# working.net
KiCad netlist of a schematic drawn in EAGLE
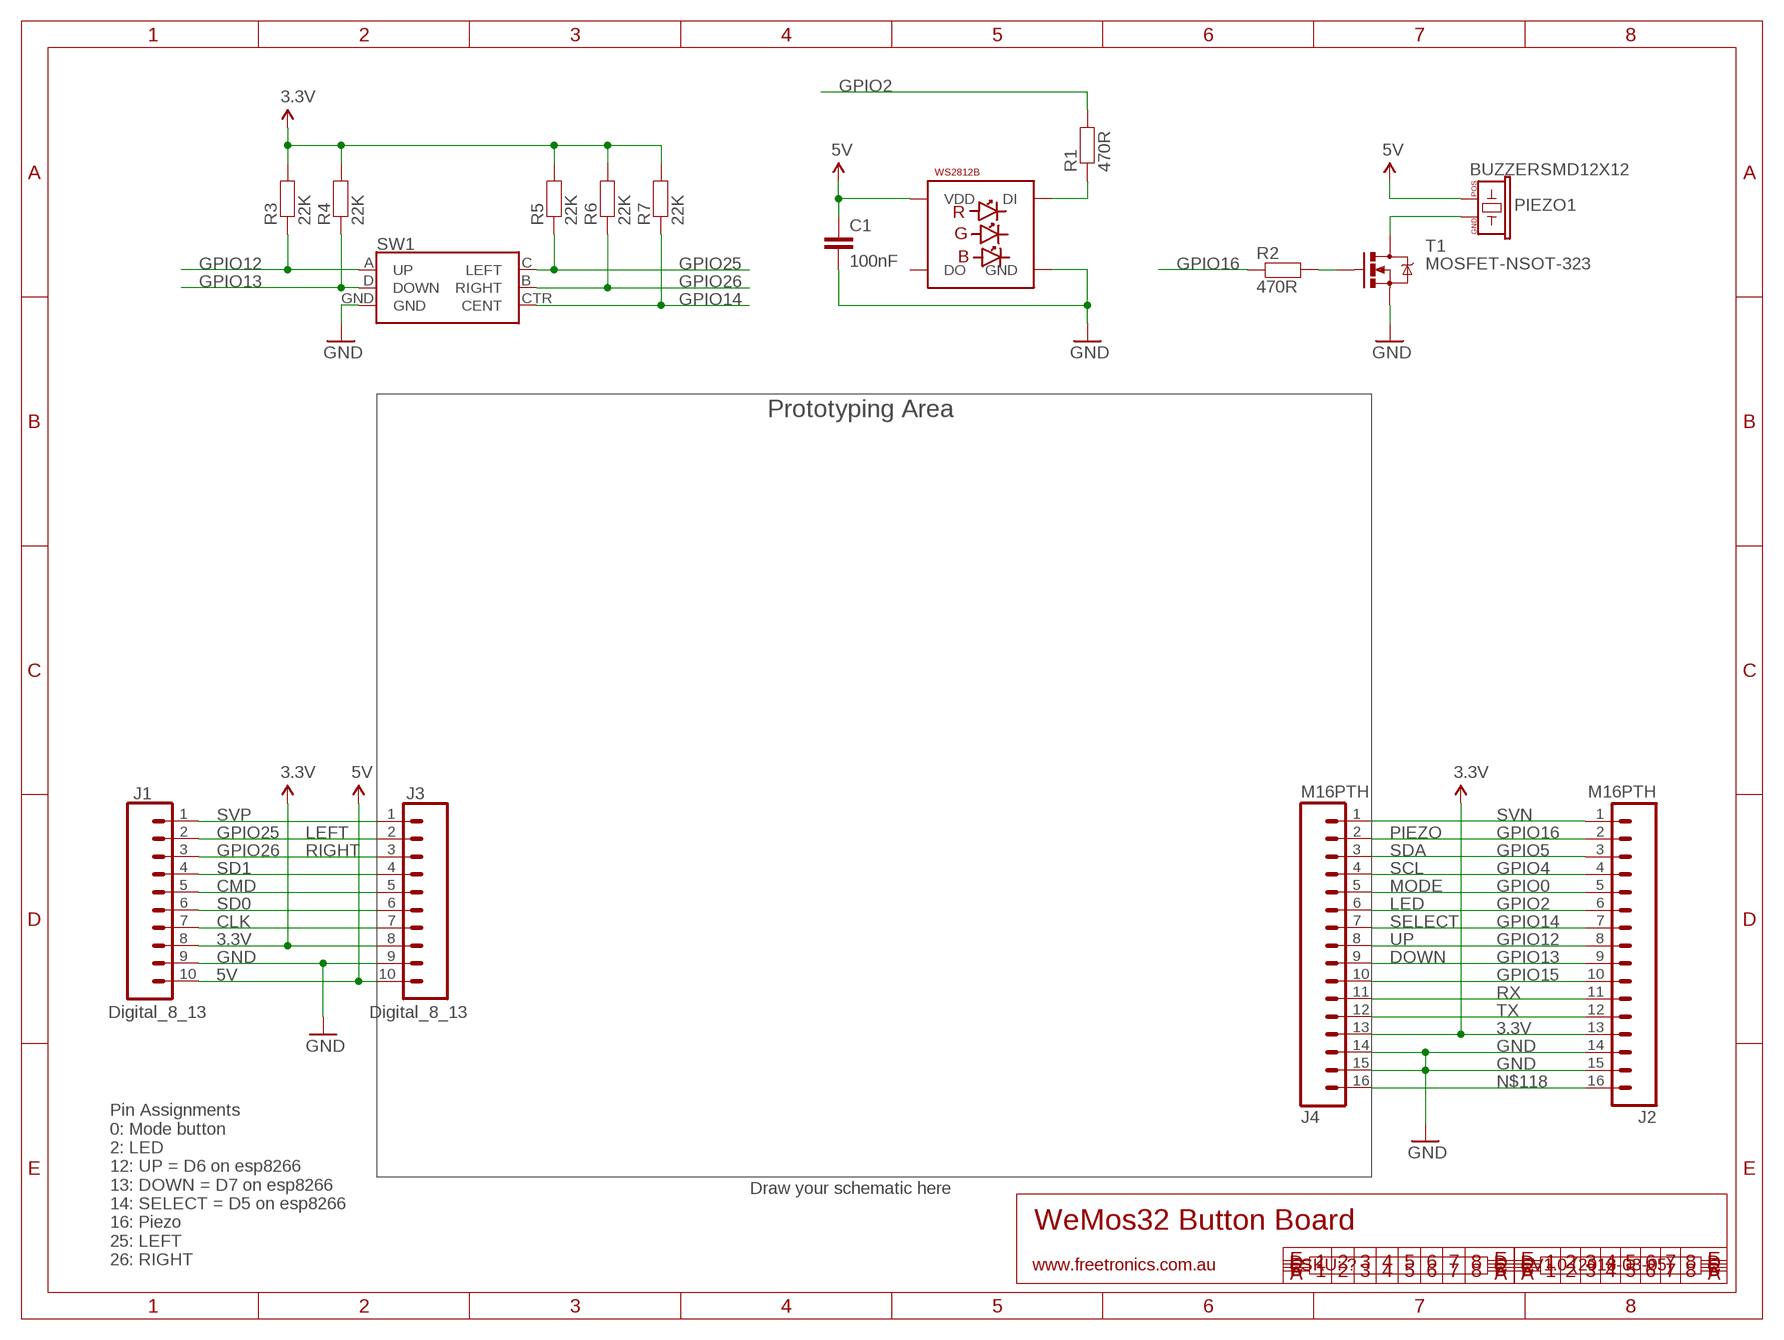
[diagram p0: schematic, sheet 1]

(export (version "E")
  (design (tool "Eeschema 10.0.6"))
  (components
    (comp (ref "C1")
      (value "100nF")
      (footprint "eagle-import:0603")
      (libsource (lib "eagle-import") (part "CAP0603"))
    )
    (comp (ref "J1")
      (value "Digital_8_13")
      (footprint "eagle-import:1X10")
      (libsource (lib "eagle-import") (part "M100.1"))
    )
    (comp (ref "J2")
      (value "M16PTH")
      (footprint "eagle-import:1X16")
      (libsource (lib "eagle-import") (part "M16PTH"))
    )
    (comp (ref "J3")
      (value "Digital_8_13")
      (footprint "eagle-import:1X10")
      (libsource (lib "eagle-import") (part "M100.1"))
    )
    (comp (ref "J4")
      (value "M16PTH")
      (footprint "eagle-import:1X16")
      (libsource (lib "eagle-import") (part "M16PTH"))
    )
    (comp (ref "LED2")
      (value "WS2812B5050")
      (footprint "eagle-import:WS2812B")
      (libsource (lib "eagle-import") (part "WS2812B5050"))
    )
    (comp (ref "PIEZO1")
      (value "BUZZERSMD12X12")
      (footprint "eagle-import:BUZZER-12X12-SMT")
      (libsource (lib "eagle-import") (part "BUZZERSMD12X12"))
    )
    (comp (ref "R1")
      (value "470R")
      (footprint "eagle-import:0603")
      (libsource (lib "eagle-import") (part "RESISTOR0603"))
    )
    (comp (ref "R2")
      (value "470R")
      (footprint "eagle-import:0603")
      (libsource (lib "eagle-import") (part "RESISTOR0603"))
    )
    (comp (ref "R3")
      (value "22K")
      (footprint "eagle-import:0603")
      (libsource (lib "eagle-import") (part "RESISTOR0603"))
    )
    (comp (ref "R4")
      (value "22K")
      (footprint "eagle-import:0603")
      (libsource (lib "eagle-import") (part "RESISTOR0603"))
    )
    (comp (ref "R5")
      (value "22K")
      (footprint "eagle-import:0603")
      (libsource (lib "eagle-import") (part "RESISTOR0603"))
    )
    (comp (ref "R6")
      (value "22K")
      (footprint "eagle-import:0603")
      (libsource (lib "eagle-import") (part "RESISTOR0603"))
    )
    (comp (ref "R7")
      (value "22K")
      (footprint "eagle-import:0603")
      (libsource (lib "eagle-import") (part "RESISTOR0603"))
    )
    (comp (ref "SW1")
      (value "JOYSTICK_MINI")
      (footprint "eagle-import:JOYSTICK_MINI")
      (libsource (lib "eagle-import") (part "JOYSTICK_MINI"))
    )
    (comp (ref "T1")
      (value "MOSFET-NSOT-323")
      (footprint "eagle-import:SOT32-3")
      (libsource (lib "eagle-import") (part "MOSFET-NSOT-323"))
    )
  )
  (nets
    (net (code "1") (name "/CLK") (class "Default")
      (node (ref "J1") (pin "7") (pinfunction "7_7") (pintype "passive"))
      (node (ref "J3") (pin "7") (pinfunction "7_7") (pintype "passive"))
    )
    (net (code "2") (name "/CMD") (class "Default")
      (node (ref "J1") (pin "5") (pinfunction "5_5") (pintype "passive"))
      (node (ref "J3") (pin "5") (pinfunction "5_5") (pintype "passive"))
    )
    (net (code "3") (name "/GPIO0") (class "Default")
      (node (ref "J2") (pin "5") (pinfunction "5_5") (pintype "passive"))
      (node (ref "J4") (pin "5") (pinfunction "5_5") (pintype "passive"))
    )
    (net (code "4") (name "/GPIO2") (class "Default")
      (node (ref "J2") (pin "6") (pinfunction "6_6") (pintype "passive"))
      (node (ref "J4") (pin "6") (pinfunction "6_6") (pintype "passive"))
      (node (ref "R1") (pin "2") (pinfunction "2_2") (pintype "passive"))
    )
    (net (code "5") (name "/GPIO4") (class "Default")
      (node (ref "J2") (pin "4") (pinfunction "4_4") (pintype "passive"))
      (node (ref "J4") (pin "4") (pinfunction "4_4") (pintype "passive"))
    )
    (net (code "6") (name "/GPIO5") (class "Default")
      (node (ref "J2") (pin "3") (pinfunction "3_3") (pintype "passive"))
      (node (ref "J4") (pin "3") (pinfunction "3_3") (pintype "passive"))
    )
    (net (code "7") (name "/GPIO12") (class "Default")
      (node (ref "J2") (pin "8") (pinfunction "8_8") (pintype "passive"))
      (node (ref "J4") (pin "8") (pinfunction "8_8") (pintype "passive"))
      (node (ref "R3") (pin "1") (pinfunction "1_1") (pintype "passive"))
      (node (ref "SW1") (pin "A") (pinfunction "UP_A") (pintype "bidirectional"))
    )
    (net (code "8") (name "/GPIO13") (class "Default")
      (node (ref "J2") (pin "9") (pinfunction "9_9") (pintype "passive"))
      (node (ref "J4") (pin "9") (pinfunction "9_9") (pintype "passive"))
      (node (ref "R4") (pin "1") (pinfunction "1_1") (pintype "passive"))
      (node (ref "SW1") (pin "D") (pinfunction "DOWN_D") (pintype "bidirectional"))
    )
    (net (code "9") (name "/GPIO14") (class "Default")
      (node (ref "J2") (pin "7") (pinfunction "7_7") (pintype "passive"))
      (node (ref "J4") (pin "7") (pinfunction "7_7") (pintype "passive"))
      (node (ref "R7") (pin "1") (pinfunction "1_1") (pintype "passive"))
      (node (ref "SW1") (pin "CTR") (pinfunction "CENT_CTR") (pintype "bidirectional"))
    )
    (net (code "10") (name "/GPIO15") (class "Default")
      (node (ref "J2") (pin "10") (pinfunction "10_10") (pintype "passive"))
      (node (ref "J4") (pin "10") (pinfunction "10_10") (pintype "passive"))
    )
    (net (code "11") (name "/GPIO16") (class "Default")
      (node (ref "J2") (pin "2") (pinfunction "2_2") (pintype "passive"))
      (node (ref "J4") (pin "2") (pinfunction "2_2") (pintype "passive"))
      (node (ref "R2") (pin "1") (pinfunction "1_1") (pintype "passive"))
    )
    (net (code "12") (name "/GPIO25") (class "Default")
      (node (ref "J1") (pin "2") (pinfunction "2_2") (pintype "passive"))
      (node (ref "J3") (pin "2") (pinfunction "2_2") (pintype "passive"))
      (node (ref "R5") (pin "1") (pinfunction "1_1") (pintype "passive"))
      (node (ref "SW1") (pin "C") (pinfunction "LEFT_C") (pintype "bidirectional"))
    )
    (net (code "13") (name "/GPIO26") (class "Default")
      (node (ref "J1") (pin "3") (pinfunction "3_3") (pintype "passive"))
      (node (ref "J3") (pin "3") (pinfunction "3_3") (pintype "passive"))
      (node (ref "R6") (pin "1") (pinfunction "1_1") (pintype "passive"))
      (node (ref "SW1") (pin "B") (pinfunction "RIGHT_B") (pintype "bidirectional"))
    )
    (net (code "14") (name "/N$118") (class "Default")
      (node (ref "J2") (pin "16") (pinfunction "16_16") (pintype "passive"))
      (node (ref "J4") (pin "16") (pinfunction "16_16") (pintype "passive"))
    )
    (net (code "15") (name "/RX") (class "Default")
      (node (ref "J2") (pin "11") (pinfunction "11_11") (pintype "passive"))
      (node (ref "J4") (pin "11") (pinfunction "11_11") (pintype "passive"))
    )
    (net (code "16") (name "/SD0") (class "Default")
      (node (ref "J1") (pin "6") (pinfunction "6_6") (pintype "passive"))
      (node (ref "J3") (pin "6") (pinfunction "6_6") (pintype "passive"))
    )
    (net (code "17") (name "/SD1") (class "Default")
      (node (ref "J1") (pin "4") (pinfunction "4_4") (pintype "passive"))
      (node (ref "J3") (pin "4") (pinfunction "4_4") (pintype "passive"))
    )
    (net (code "18") (name "/SVN") (class "Default")
      (node (ref "J2") (pin "1") (pinfunction "1_1") (pintype "passive"))
      (node (ref "J4") (pin "1") (pinfunction "1_1") (pintype "passive"))
    )
    (net (code "19") (name "/SVP") (class "Default")
      (node (ref "J1") (pin "1") (pinfunction "1_1") (pintype "passive"))
      (node (ref "J3") (pin "1") (pinfunction "1_1") (pintype "passive"))
    )
    (net (code "20") (name "/TX") (class "Default")
      (node (ref "J2") (pin "12") (pinfunction "12_12") (pintype "passive"))
      (node (ref "J4") (pin "12") (pinfunction "12_12") (pintype "passive"))
    )
    (net (code "21") (name "3.3V") (class "Default")
      (node (ref "J1") (pin "8") (pinfunction "8_8") (pintype "passive"))
      (node (ref "J2") (pin "13") (pinfunction "13_13") (pintype "passive"))
      (node (ref "J3") (pin "8") (pinfunction "8_8") (pintype "passive"))
      (node (ref "J4") (pin "13") (pinfunction "13_13") (pintype "passive"))
      (node (ref "R3") (pin "2") (pinfunction "2_2") (pintype "passive"))
      (node (ref "R4") (pin "2") (pinfunction "2_2") (pintype "passive"))
      (node (ref "R5") (pin "2") (pinfunction "2_2") (pintype "passive"))
      (node (ref "R6") (pin "2") (pinfunction "2_2") (pintype "passive"))
      (node (ref "R7") (pin "2") (pinfunction "2_2") (pintype "passive"))
    )
    (net (code "22") (name "5V") (class "Default")
      (node (ref "C1") (pin "1") (pinfunction "1_1") (pintype "passive"))
      (node (ref "J1") (pin "10") (pinfunction "10_10") (pintype "passive"))
      (node (ref "J3") (pin "10") (pinfunction "10_10") (pintype "passive"))
      (node (ref "LED2") (pin "1-VDD") (pinfunction "VDD_1-VDD") (pintype "power_in"))
      (node (ref "PIEZO1") (pin "2") (pinfunction "POS_2") (pintype "passive"))
    )
    (net (code "23") (name "GND") (class "Default")
      (node (ref "C1") (pin "2") (pinfunction "2_2") (pintype "passive"))
      (node (ref "J1") (pin "9") (pinfunction "9_9") (pintype "passive"))
      (node (ref "J2") (pin "14") (pinfunction "14_14") (pintype "passive"))
      (node (ref "J2") (pin "15") (pinfunction "15_15") (pintype "passive"))
      (node (ref "J3") (pin "9") (pinfunction "9_9") (pintype "passive"))
      (node (ref "J4") (pin "14") (pinfunction "14_14") (pintype "passive"))
      (node (ref "J4") (pin "15") (pinfunction "15_15") (pintype "passive"))
      (node (ref "LED2") (pin "3-GND") (pinfunction "GND_3-GND") (pintype "power_in"))
      (node (ref "SW1") (pin "GND") (pinfunction "GND_GND") (pintype "bidirectional"))
      (node (ref "T1") (pin "2") (pinfunction "S_2") (pintype "passive"))
    )
    (net (code "24") (name "Net-(LED2-DI)") (class "Default")
      (node (ref "LED2") (pin "4-DIN") (pinfunction "DI_4-DIN") (pintype "input"))
      (node (ref "R1") (pin "1") (pinfunction "1_1") (pintype "passive"))
    )
    (net (code "25") (name "Net-(PIEZO1-GND)") (class "Default")
      (node (ref "PIEZO1") (pin "1") (pinfunction "GND_1") (pintype "passive"))
      (node (ref "T1") (pin "3") (pinfunction "D_3") (pintype "passive"))
    )
    (net (code "26") (name "Net-(T1-G)") (class "Default")
      (node (ref "R2") (pin "2") (pinfunction "2_2") (pintype "passive"))
      (node (ref "T1") (pin "1") (pinfunction "G_1") (pintype "passive"))
    )
    (net (code "27") (name "unconnected-(LED2-DO-Pad2-DOUT)") (class "Default")
      (node (ref "LED2") (pin "2-DOUT") (pinfunction "DO_2-DOUT") (pintype "output"))
    )
  )
)
